# RAMBoSCadapter.net
KiCad netlist of a schematic drawn in EAGLE
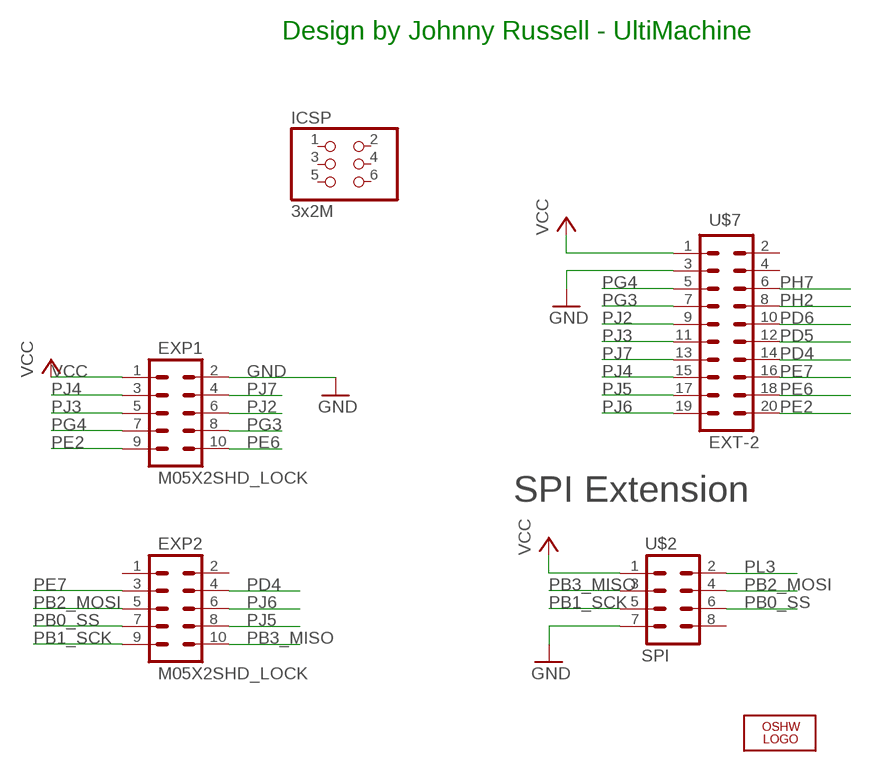
[diagram p0: schematic, sheet 1]

(export (version "E")
  (design (tool "Eeschema 10.0.6"))
  (components
    (comp (ref "EXP1")
      (value "M05X2SHD_LOCK")
      (footprint "eagle-import:2X5-SHROUDED_LOCK")
      (libsource (lib "eagle-import") (part "M05X2SHD_LOCK"))
    )
    (comp (ref "EXP2")
      (value "M05X2SHD_LOCK")
      (footprint "eagle-import:2X5-SHROUDED_LOCK")
      (libsource (lib "eagle-import") (part "M05X2SHD_LOCK"))
    )
    (comp (ref "ICSP")
      (value "3x2M")
      (footprint "eagle-import:2X03")
      (libsource (lib "eagle-import") (part "PINHD-2X3"))
    )
    (comp (ref "LOGO1")
      (value "OSHW_LOGO_8MILX0150-NT")
      (footprint "eagle-import:OSHW_8X150_NOTEXT")
      (libsource (lib "eagle-import") (part "OSHW_LOGO_8MILX0150-NT"))
    )
    (comp (ref "U$2")
      (value "SPI")
      (footprint "eagle-import:2X4")
      (libsource (lib "eagle-import") (part "M04X2"))
    )
    (comp (ref "U$7")
      (value "EXT-2")
      (footprint "eagle-import:2X10")
      (libsource (lib "eagle-import") (part "M10X2"))
    )
  )
  (nets
    (net (code "1") (name "/PB0_SS") (class "Default")
      (node (ref "EXP2") (pin "7") (pinfunction "7_7") (pintype "passive"))
      (node (ref "U$2") (pin "6") (pinfunction "6_6") (pintype "passive"))
    )
    (net (code "2") (name "/PB1_SCK") (class "Default")
      (node (ref "EXP2") (pin "9") (pinfunction "9_9") (pintype "passive"))
      (node (ref "U$2") (pin "5") (pinfunction "5_5") (pintype "passive"))
    )
    (net (code "3") (name "/PB2_MOSI") (class "Default")
      (node (ref "EXP2") (pin "5") (pinfunction "5_5") (pintype "passive"))
      (node (ref "U$2") (pin "4") (pinfunction "4_4") (pintype "passive"))
    )
    (net (code "4") (name "/PB3_MISO") (class "Default")
      (node (ref "EXP2") (pin "10") (pinfunction "10_10") (pintype "passive"))
      (node (ref "U$2") (pin "3") (pinfunction "3_3") (pintype "passive"))
    )
    (net (code "5") (name "/PD4") (class "Default")
      (node (ref "EXP2") (pin "4") (pinfunction "4_4") (pintype "passive"))
      (node (ref "U$7") (pin "14") (pinfunction "14_14") (pintype "passive"))
    )
    (net (code "6") (name "/PD5") (class "Default")
      (node (ref "U$7") (pin "12") (pinfunction "12_12") (pintype "passive"))
    )
    (net (code "7") (name "/PD6") (class "Default")
      (node (ref "U$7") (pin "10") (pinfunction "10_10") (pintype "passive"))
    )
    (net (code "8") (name "/PE2") (class "Default")
      (node (ref "EXP1") (pin "9") (pinfunction "9_9") (pintype "passive"))
      (node (ref "U$7") (pin "20") (pinfunction "20_20") (pintype "passive"))
    )
    (net (code "9") (name "/PE6") (class "Default")
      (node (ref "EXP1") (pin "10") (pinfunction "10_10") (pintype "passive"))
      (node (ref "U$7") (pin "18") (pinfunction "18_18") (pintype "passive"))
    )
    (net (code "10") (name "/PE7") (class "Default")
      (node (ref "EXP2") (pin "3") (pinfunction "3_3") (pintype "passive"))
      (node (ref "U$7") (pin "16") (pinfunction "16_16") (pintype "passive"))
    )
    (net (code "11") (name "/PG3") (class "Default")
      (node (ref "EXP1") (pin "8") (pinfunction "8_8") (pintype "passive"))
      (node (ref "U$7") (pin "7") (pinfunction "7_7") (pintype "passive"))
    )
    (net (code "12") (name "/PG4") (class "Default")
      (node (ref "EXP1") (pin "7") (pinfunction "7_7") (pintype "passive"))
      (node (ref "U$7") (pin "5") (pinfunction "5_5") (pintype "passive"))
    )
    (net (code "13") (name "/PH2") (class "Default")
      (node (ref "U$7") (pin "8") (pinfunction "8_8") (pintype "passive"))
    )
    (net (code "14") (name "/PH7") (class "Default")
      (node (ref "U$7") (pin "6") (pinfunction "6_6") (pintype "passive"))
    )
    (net (code "15") (name "/PJ2") (class "Default")
      (node (ref "EXP1") (pin "6") (pinfunction "6_6") (pintype "passive"))
      (node (ref "U$7") (pin "9") (pinfunction "9_9") (pintype "passive"))
    )
    (net (code "16") (name "/PJ3") (class "Default")
      (node (ref "EXP1") (pin "5") (pinfunction "5_5") (pintype "passive"))
      (node (ref "U$7") (pin "11") (pinfunction "11_11") (pintype "passive"))
    )
    (net (code "17") (name "/PJ4") (class "Default")
      (node (ref "EXP1") (pin "3") (pinfunction "3_3") (pintype "passive"))
      (node (ref "U$7") (pin "15") (pinfunction "15_15") (pintype "passive"))
    )
    (net (code "18") (name "/PJ5") (class "Default")
      (node (ref "EXP2") (pin "8") (pinfunction "8_8") (pintype "passive"))
      (node (ref "U$7") (pin "17") (pinfunction "17_17") (pintype "passive"))
    )
    (net (code "19") (name "/PJ6") (class "Default")
      (node (ref "EXP2") (pin "6") (pinfunction "6_6") (pintype "passive"))
      (node (ref "U$7") (pin "19") (pinfunction "19_19") (pintype "passive"))
    )
    (net (code "20") (name "/PJ7") (class "Default")
      (node (ref "EXP1") (pin "4") (pinfunction "4_4") (pintype "passive"))
      (node (ref "U$7") (pin "13") (pinfunction "13_13") (pintype "passive"))
    )
    (net (code "21") (name "/PL3") (class "Default")
      (node (ref "U$2") (pin "2") (pinfunction "2_2") (pintype "passive"))
    )
    (net (code "22") (name "GND") (class "Default")
      (node (ref "EXP1") (pin "2") (pinfunction "2_2") (pintype "passive"))
      (node (ref "U$2") (pin "7") (pinfunction "7_7") (pintype "passive"))
      (node (ref "U$7") (pin "3") (pinfunction "3_3") (pintype "passive"))
    )
    (net (code "23") (name "VCC") (class "Default")
      (node (ref "EXP1") (pin "1") (pinfunction "1_1") (pintype "passive"))
      (node (ref "U$2") (pin "1") (pinfunction "1_1") (pintype "passive"))
      (node (ref "U$7") (pin "1") (pinfunction "1_1") (pintype "passive"))
    )
    (net (code "24") (name "unconnected-(EXP2-Pad1)") (class "Default")
      (node (ref "EXP2") (pin "1") (pinfunction "1_1") (pintype "passive"))
    )
    (net (code "25") (name "unconnected-(EXP2-Pad2)") (class "Default")
      (node (ref "EXP2") (pin "2") (pinfunction "2_2") (pintype "passive"))
    )
    (net (code "26") (name "unconnected-(ICSP-Pad1)") (class "Default")
      (node (ref "ICSP") (pin "1") (pinfunction "1_1") (pintype "passive"))
    )
    (net (code "27") (name "unconnected-(ICSP-Pad2)") (class "Default")
      (node (ref "ICSP") (pin "2") (pinfunction "2_2") (pintype "passive"))
    )
    (net (code "28") (name "unconnected-(ICSP-Pad3)") (class "Default")
      (node (ref "ICSP") (pin "3") (pinfunction "3_3") (pintype "passive"))
    )
    (net (code "29") (name "unconnected-(ICSP-Pad4)") (class "Default")
      (node (ref "ICSP") (pin "4") (pinfunction "4_4") (pintype "passive"))
    )
    (net (code "30") (name "unconnected-(ICSP-Pad5)") (class "Default")
      (node (ref "ICSP") (pin "5") (pinfunction "5_5") (pintype "passive"))
    )
    (net (code "31") (name "unconnected-(ICSP-Pad6)") (class "Default")
      (node (ref "ICSP") (pin "6") (pinfunction "6_6") (pintype "passive"))
    )
    (net (code "32") (name "unconnected-(U$2-Pad8)") (class "Default")
      (node (ref "U$2") (pin "8") (pinfunction "8_8") (pintype "passive"))
    )
    (net (code "33") (name "unconnected-(U$7-Pad2)") (class "Default")
      (node (ref "U$7") (pin "2") (pinfunction "2_2") (pintype "passive"))
    )
    (net (code "34") (name "unconnected-(U$7-Pad4)") (class "Default")
      (node (ref "U$7") (pin "4") (pinfunction "4_4") (pintype "passive"))
    )
  )
)
